# FuelGauge_Sheet.net
KiCad netlist of a schematic drawn in Altium Designer
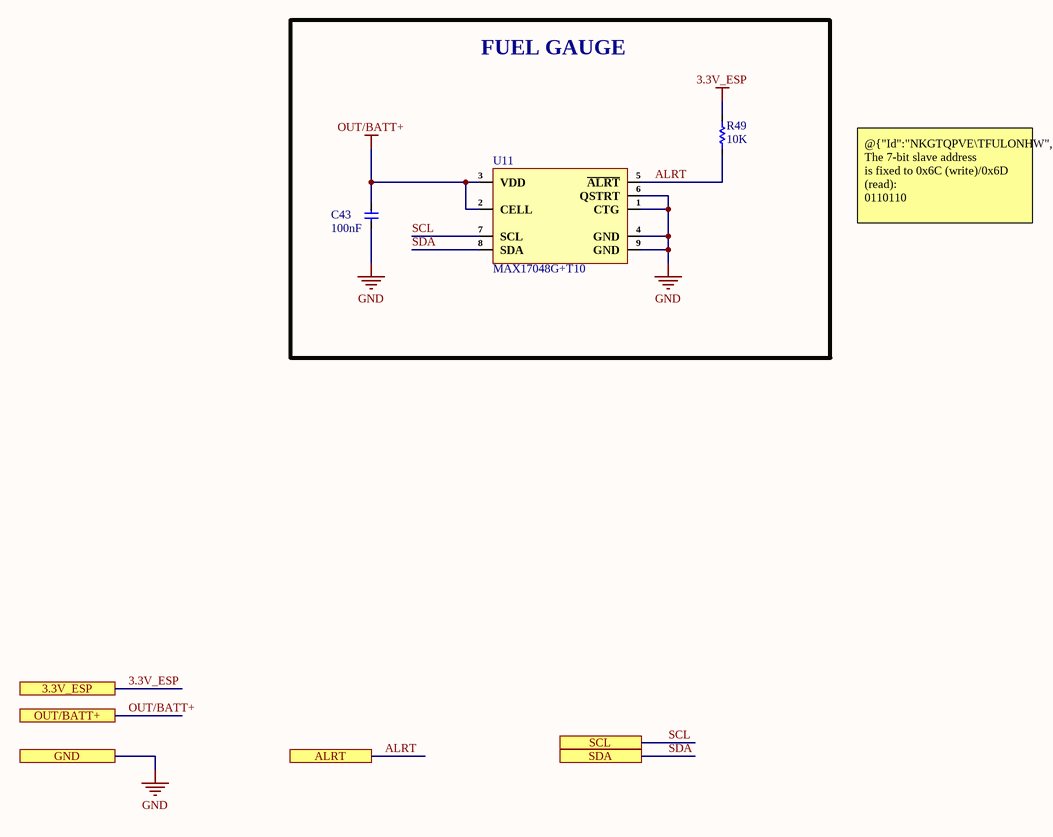
[diagram p0: FuelGauge_Sheet.SchDoc]

(export (version "E")
  (design (tool "Eeschema 10.0.6"))
  (components
    (comp (ref "C43")
      (value "100nF")
      (footprint "cap-0402")
      (description "CAP CER 0.1UF 50V X7R 0402")
      (fields
        (field (name "MANUFACTURER") "TDK")
        (field (name "MANUFACTURER PART NUMBER") "C1005X7R1H104KT000F")
      )
      (libsource (lib "eSpark Libraries") (part "C1005X7R1H104KT000F"))
    )
    (comp (ref "R49")
      (value "10K")
      (footprint "Res-0402")
      (description "RES 10K OHM 1% 1/16W 0402")
      (fields
        (field (name "MANUFACTURER") "Yageo")
        (field (name "MANUFACTURER PART NUMBER") "RC0402FR-0710KL")
      )
      (libsource (lib "eSpark Libraries") (part "RC0402FR-0710KL"))
    )
    (comp (ref "U11")
      (value "MAX17048G+T10")
      (footprint "8-TDFN-EP (2x2)")
      (description "IC BATT MON LI-ION 1CELL 8TDFN")
      (fields (field (name "MANUFACTURER") "Maxim") (field (name "LCSC PART NUMBER") "C2682616"))
      (libsource (lib "eSpark Libraries") (part "MAX17048G+T10"))
    )
  )
  (nets
    (net (code "1") (name "/ALRT") (class "Default")
      (node (ref "R49") (pin "1") (pinfunction "1_1") (pintype "passive"))
      (node (ref "U11") (pin "5") (pinfunction "~{ALRT}_5") (pintype "passive"))
    )
    (net (code "2") (name "/SCL") (class "Default")
      (node (ref "U11") (pin "7") (pinfunction "SCL_7") (pintype "passive"))
    )
    (net (code "3") (name "/SDA") (class "Default")
      (node (ref "U11") (pin "8") (pinfunction "SDA_8") (pintype "passive"))
    )
    (net (code "4") (name "3.3V_ESP") (class "Default")
      (node (ref "R49") (pin "2") (pinfunction "2_2") (pintype "passive"))
    )
    (net (code "5") (name "GND") (class "Default")
      (node (ref "C43") (pin "2") (pinfunction "2_2") (pintype "passive"))
      (node (ref "U11") (pin "1") (pinfunction "CTG_1") (pintype "passive"))
      (node (ref "U11") (pin "4") (pinfunction "GND_4") (pintype "passive"))
      (node (ref "U11") (pin "6") (pinfunction "QSTRT_6") (pintype "passive"))
      (node (ref "U11") (pin "9") (pinfunction "GND_9") (pintype "passive"))
    )
    (net (code "6") (name "OUT{slash}BATT+") (class "Default")
      (node (ref "C43") (pin "1") (pinfunction "1_1") (pintype "passive"))
      (node (ref "U11") (pin "2") (pinfunction "CELL_2") (pintype "passive"))
      (node (ref "U11") (pin "3") (pinfunction "VDD_3") (pintype "passive"))
    )
  )
)
